# pblaze_ext.net
KiCad netlist of a schematic drawn in Altium Designer
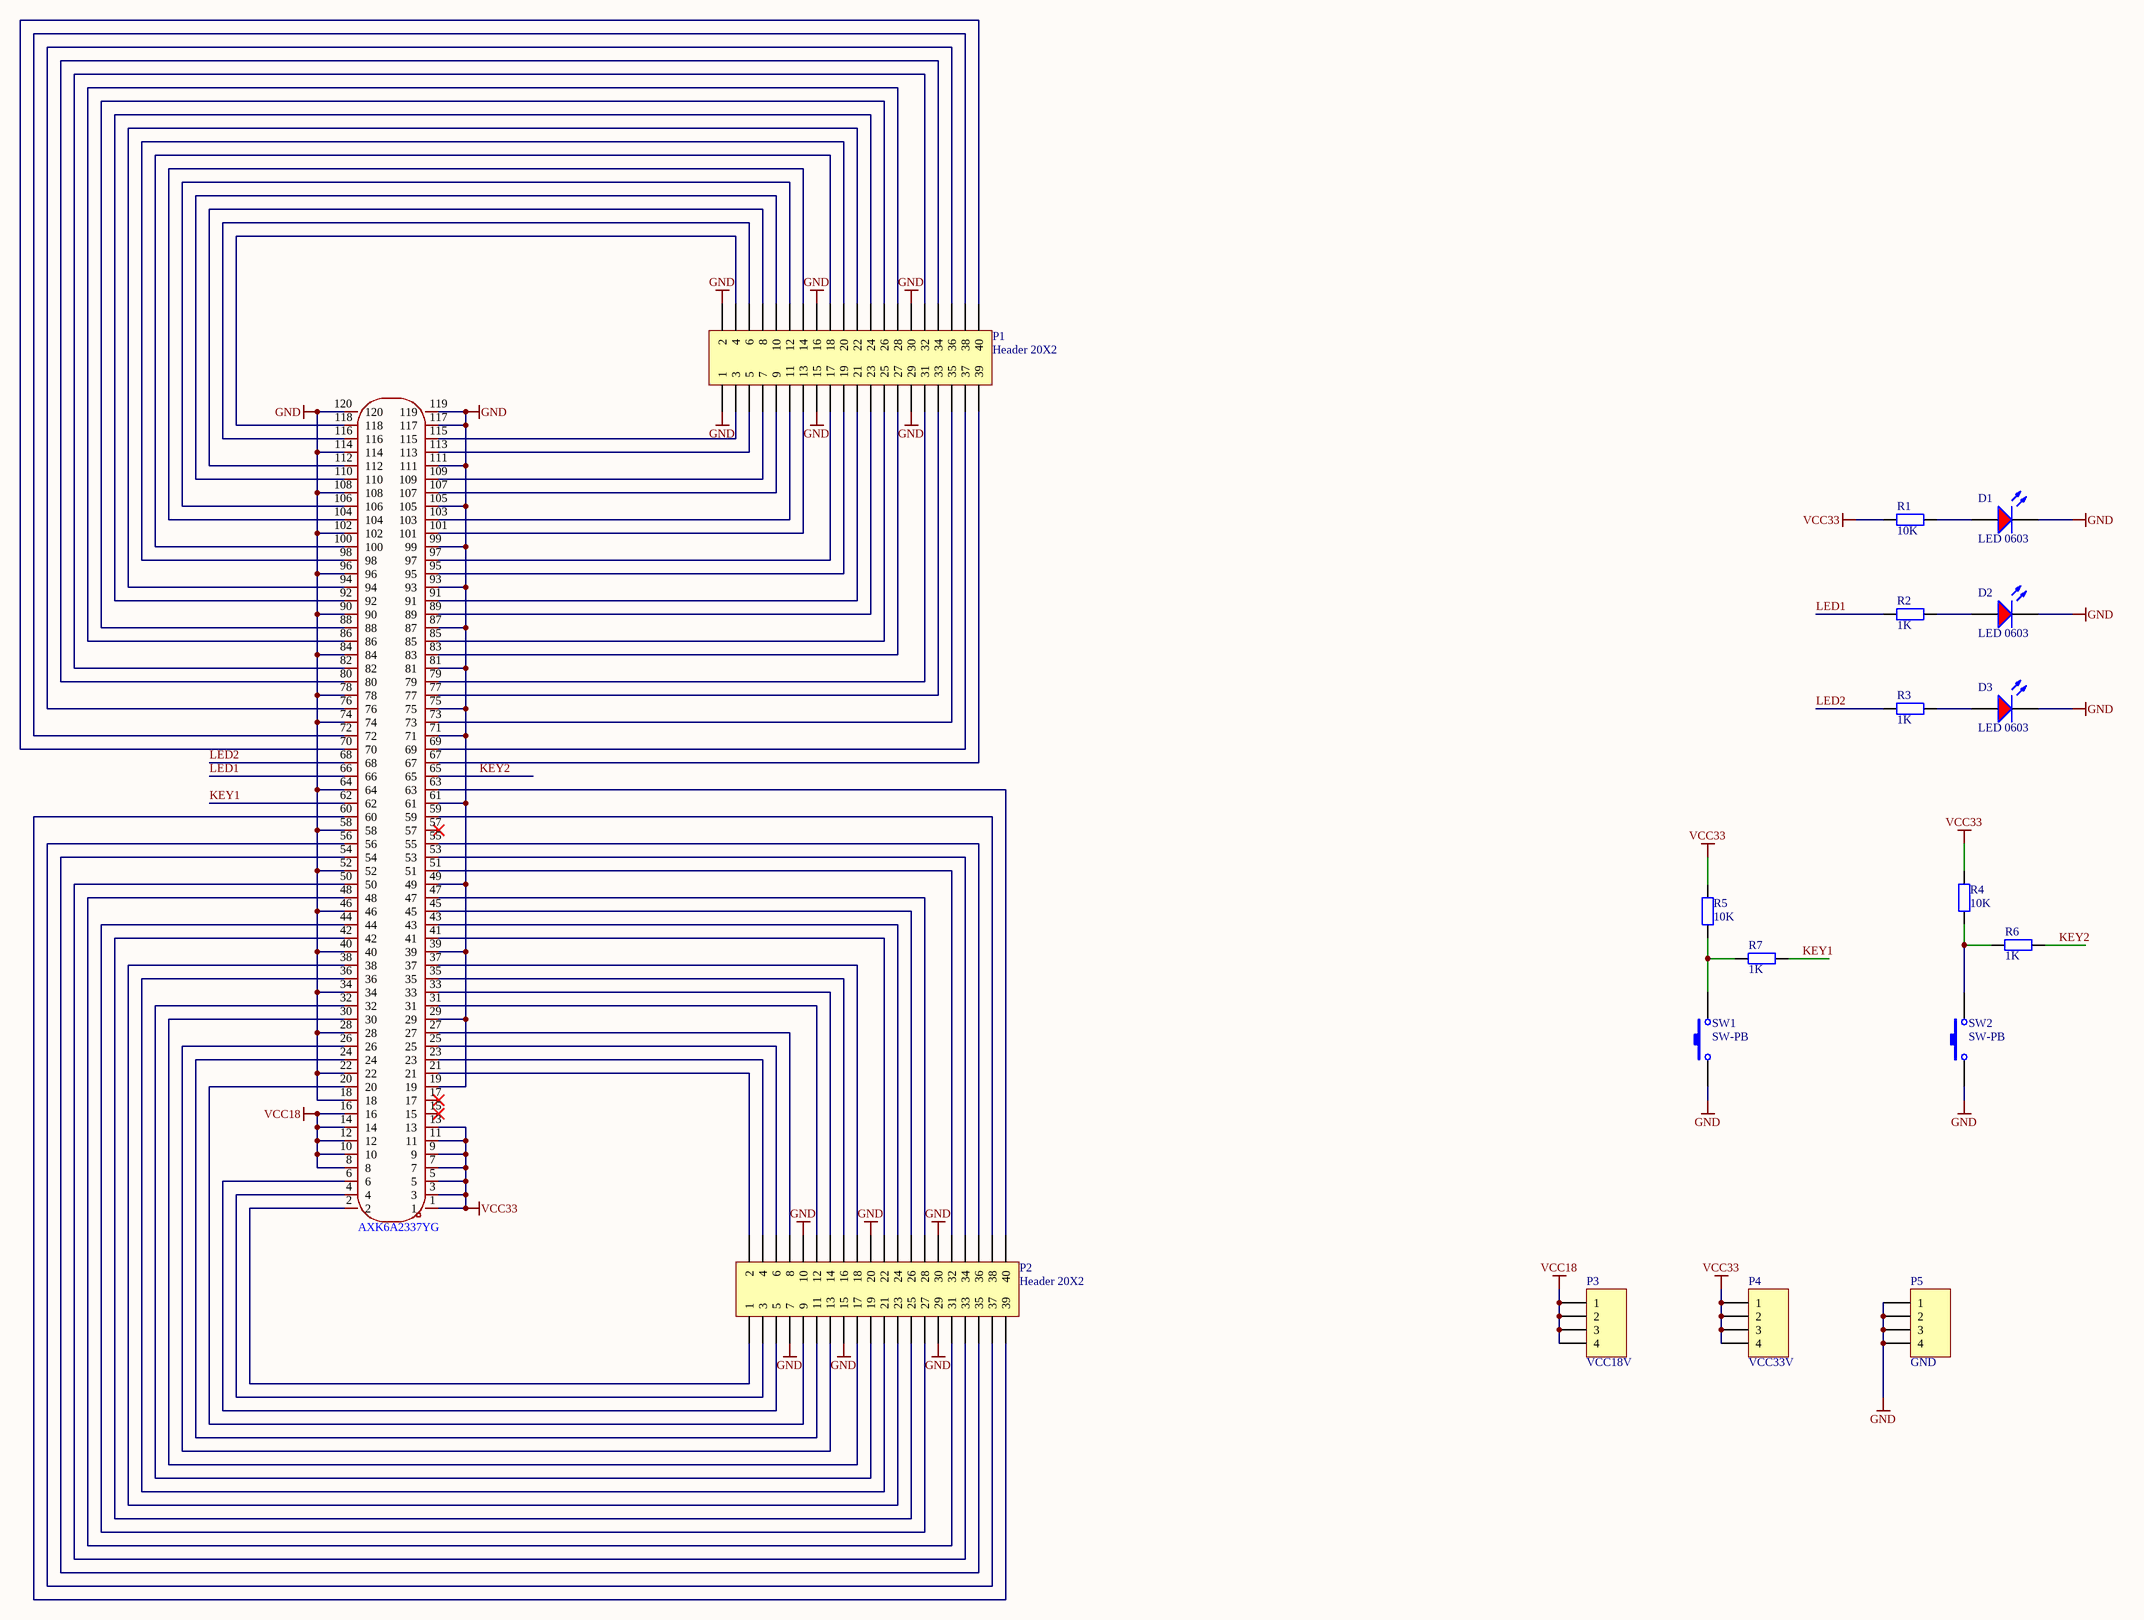
[diagram p0: pblaze_ext.schdoc]

(export (version "E")
  (design (tool "Eeschema 10.0.6"))
  (components
    (comp (ref "D1")
      (value "LED 0603")
      (footprint "0603_LED_S1")
      (description "发光二极管")
      (libsource (lib "Miscellaneous Devices LC") (part "0603 红灯"))
    )
    (comp (ref "D2")
      (value "LED 0603")
      (footprint "0603_LED_S1")
      (description "发光二极管")
      (libsource (lib "Miscellaneous Devices LC") (part "0603 红灯"))
    )
    (comp (ref "D3")
      (value "LED 0603")
      (footprint "0603_LED_S1")
      (description "发光二极管")
      (libsource (lib "Miscellaneous Devices LC") (part "0603 红灯"))
    )
    (comp (ref "P1")
      (value "Header 20X2")
      (footprint "HDR2X20")
      (description "Header, 20-Pin, Dual row")
      (fields (field (name "PUBLISHER") "Altium Limited"))
      (libsource (lib "Miscellaneous Connectors") (part "Header 20X2"))
    )
    (comp (ref "P2")
      (value "Header 20X2")
      (footprint "HDR2X20")
      (description "Header, 20-Pin, Dual row")
      (fields (field (name "PUBLISHER") "Altium Limited"))
      (libsource (lib "Miscellaneous Connectors") (part "Header 20X2"))
    )
    (comp (ref "P3")
      (value "VCC18V")
      (footprint "HDR1X4")
      (description "Header, 4-Pin")
      (fields (field (name "PUBLISHER") "Altium Limited"))
      (libsource (lib "Miscellaneous Connectors") (part "Header 4"))
    )
    (comp (ref "P4")
      (value "VCC33V")
      (footprint "HDR1X4")
      (description "Header, 4-Pin")
      (fields (field (name "PUBLISHER") "Altium Limited"))
      (libsource (lib "Miscellaneous Connectors") (part "Header 4"))
    )
    (comp (ref "P5")
      (value "GND")
      (footprint "HDR1X4")
      (description "Header, 4-Pin")
      (fields (field (name "PUBLISHER") "Altium Limited"))
      (libsource (lib "Miscellaneous Connectors") (part "Header 4"))
    )
    (comp (ref "R1")
      (value "10K")
      (footprint "0603_R")
      (description "贴片电阻")
      (libsource (lib "Miscellaneous Devices LC") (part "0603 1KΩ (1001) 1%"))
    )
    (comp (ref "R2")
      (value "1K")
      (footprint "0603_R")
      (description "贴片电阻")
      (libsource (lib "Miscellaneous Devices LC") (part "0603 1KΩ (1001) 1%"))
    )
    (comp (ref "R3")
      (value "1K")
      (footprint "0603_R")
      (description "贴片电阻")
      (libsource (lib "Miscellaneous Devices LC") (part "0603 1KΩ (1001) 1%"))
    )
    (comp (ref "R4")
      (value "10K")
      (footprint "0603_R")
      (description "贴片电阻")
      (libsource (lib "") (part "0603 1KΩ (1001) 1%_2"))
    )
    (comp (ref "R5")
      (value "10K")
      (footprint "0603_R")
      (description "贴片电阻")
      (libsource (lib "") (part "0603 1KΩ (1001) 1%_2"))
    )
    (comp (ref "R6")
      (value "1K")
      (footprint "0603_R")
      (description "贴片电阻")
      (libsource (lib "") (part "0603 1KΩ (1001) 1%_1"))
    )
    (comp (ref "R7")
      (value "1K")
      (footprint "0603_R")
      (description "贴片电阻")
      (libsource (lib "") (part "0603 1KΩ (1001) 1%_1"))
    )
    (comp (ref "SW1")
      (value "SW-PB")
      (footprint "SW-2- 3.8X7.6-S")
      (description "按钮开关")
      (fields (field (name "更新者") "安菲"))
      (libsource (lib "其他") (part "SW-PB"))
    )
    (comp (ref "SW2")
      (value "SW-PB")
      (footprint "SW-2- 3.8X7.6-S")
      (description "按钮开关")
      (fields (field (name "更新者") "安菲"))
      (libsource (lib "其他") (part "SW-PB"))
    )
    (comp (ref "U1")
      (value "AXK6A2337YG")
      (footprint "CONN-SMD_120P-P0.50_AXK6A2337YG")
      (fields (field (name "MANUFACTURER") "PANASONIC(松下)"))
      (libsource (lib "altium-import") (part "root_2_AXK6A2337YG_"))
    )
  )
  (nets
    (net (code "1") (name "/KEY1") (class "Default")
      (node (ref "R7") (pin "1") (pinfunction "1_1") (pintype "passive"))
      (node (ref "U1") (pin "62") (pinfunction "62_62") (pintype "passive"))
    )
    (net (code "2") (name "/KEY2") (class "Default")
      (node (ref "R6") (pin "1") (pinfunction "1_1") (pintype "passive"))
      (node (ref "U1") (pin "65") (pinfunction "65_65") (pintype "passive"))
    )
    (net (code "3") (name "/LED1") (class "Default")
      (node (ref "R2") (pin "1") (pinfunction "1_1") (pintype "passive"))
      (node (ref "U1") (pin "66") (pinfunction "66_66") (pintype "passive"))
    )
    (net (code "4") (name "/LED2") (class "Default")
      (node (ref "R3") (pin "1") (pinfunction "1_1") (pintype "passive"))
      (node (ref "U1") (pin "68") (pinfunction "68_68") (pintype "passive"))
    )
    (net (code "5") (name "GND") (class "Default")
      (node (ref "D1") (pin "K") (pinfunction "K_K") (pintype "passive"))
      (node (ref "D2") (pin "K") (pinfunction "K_K") (pintype "passive"))
      (node (ref "D3") (pin "K") (pinfunction "K_K") (pintype "passive"))
      (node (ref "P1") (pin "1") (pinfunction "1_1") (pintype "passive"))
      (node (ref "P1") (pin "15") (pinfunction "15_15") (pintype "passive"))
      (node (ref "P1") (pin "16") (pinfunction "16_16") (pintype "passive"))
      (node (ref "P1") (pin "2") (pinfunction "2_2") (pintype "passive"))
      (node (ref "P1") (pin "29") (pinfunction "29_29") (pintype "passive"))
      (node (ref "P1") (pin "30") (pinfunction "30_30") (pintype "passive"))
      (node (ref "P2") (pin "10") (pinfunction "10_10") (pintype "passive"))
      (node (ref "P2") (pin "15") (pinfunction "15_15") (pintype "passive"))
      (node (ref "P2") (pin "20") (pinfunction "20_20") (pintype "passive"))
      (node (ref "P2") (pin "29") (pinfunction "29_29") (pintype "passive"))
      (node (ref "P2") (pin "30") (pinfunction "30_30") (pintype "passive"))
      (node (ref "P2") (pin "7") (pinfunction "7_7") (pintype "passive"))
      (node (ref "P5") (pin "1") (pinfunction "1_1") (pintype "passive"))
      (node (ref "P5") (pin "2") (pinfunction "2_2") (pintype "passive"))
      (node (ref "P5") (pin "3") (pinfunction "3_3") (pintype "passive"))
      (node (ref "P5") (pin "4") (pinfunction "4_4") (pintype "passive"))
      (node (ref "SW1") (pin "1") (pinfunction "1_1") (pintype "passive"))
      (node (ref "SW2") (pin "1") (pinfunction "1_1") (pintype "passive"))
      (node (ref "U1") (pin "102") (pinfunction "102_102") (pintype "passive"))
      (node (ref "U1") (pin "105") (pinfunction "105_105") (pintype "passive"))
      (node (ref "U1") (pin "108") (pinfunction "108_108") (pintype "passive"))
      (node (ref "U1") (pin "111") (pinfunction "111_111") (pintype "passive"))
      (node (ref "U1") (pin "114") (pinfunction "114_114") (pintype "passive"))
      (node (ref "U1") (pin "117") (pinfunction "117_117") (pintype "passive"))
      (node (ref "U1") (pin "119") (pinfunction "119_119") (pintype "passive"))
      (node (ref "U1") (pin "120") (pinfunction "120_120") (pintype "passive"))
      (node (ref "U1") (pin "18") (pinfunction "18_18") (pintype "passive"))
      (node (ref "U1") (pin "19") (pinfunction "19_19") (pintype "passive"))
      (node (ref "U1") (pin "22") (pinfunction "22_22") (pintype "passive"))
      (node (ref "U1") (pin "28") (pinfunction "28_28") (pintype "passive"))
      (node (ref "U1") (pin "29") (pinfunction "29_29") (pintype "passive"))
      (node (ref "U1") (pin "34") (pinfunction "34_34") (pintype "passive"))
      (node (ref "U1") (pin "39") (pinfunction "39_39") (pintype "passive"))
      (node (ref "U1") (pin "40") (pinfunction "40_40") (pintype "passive"))
      (node (ref "U1") (pin "46") (pinfunction "46_46") (pintype "passive"))
      (node (ref "U1") (pin "49") (pinfunction "49_49") (pintype "passive"))
      (node (ref "U1") (pin "52") (pinfunction "52_52") (pintype "passive"))
      (node (ref "U1") (pin "58") (pinfunction "58_58") (pintype "passive"))
      (node (ref "U1") (pin "61") (pinfunction "61_61") (pintype "passive"))
      (node (ref "U1") (pin "64") (pinfunction "64_64") (pintype "passive"))
      (node (ref "U1") (pin "71") (pinfunction "71_71") (pintype "passive"))
      (node (ref "U1") (pin "74") (pinfunction "74_74") (pintype "passive"))
      (node (ref "U1") (pin "75") (pinfunction "75_75") (pintype "passive"))
      (node (ref "U1") (pin "78") (pinfunction "78_78") (pintype "passive"))
      (node (ref "U1") (pin "81") (pinfunction "81_81") (pintype "passive"))
      (node (ref "U1") (pin "84") (pinfunction "84_84") (pintype "passive"))
      (node (ref "U1") (pin "87") (pinfunction "87_87") (pintype "passive"))
      (node (ref "U1") (pin "90") (pinfunction "90_90") (pintype "passive"))
      (node (ref "U1") (pin "93") (pinfunction "93_93") (pintype "passive"))
      (node (ref "U1") (pin "96") (pinfunction "96_96") (pintype "passive"))
      (node (ref "U1") (pin "99") (pinfunction "99_99") (pintype "passive"))
    )
    (net (code "6") (name "Net-(D1-PadA)") (class "Default")
      (node (ref "D1") (pin "A") (pinfunction "A_A") (pintype "passive"))
      (node (ref "R1") (pin "2") (pinfunction "2_2") (pintype "passive"))
    )
    (net (code "7") (name "Net-(D2-PadA)") (class "Default")
      (node (ref "D2") (pin "A") (pinfunction "A_A") (pintype "passive"))
      (node (ref "R2") (pin "2") (pinfunction "2_2") (pintype "passive"))
    )
    (net (code "8") (name "Net-(D3-PadA)") (class "Default")
      (node (ref "D3") (pin "A") (pinfunction "A_A") (pintype "passive"))
      (node (ref "R3") (pin "2") (pinfunction "2_2") (pintype "passive"))
    )
    (net (code "9") (name "Net-(P1-Pad3)") (class "Default")
      (node (ref "P1") (pin "3") (pinfunction "3_3") (pintype "passive"))
      (node (ref "U1") (pin "115") (pinfunction "115_115") (pintype "passive"))
    )
    (net (code "10") (name "Net-(P1-Pad4)") (class "Default")
      (node (ref "P1") (pin "4") (pinfunction "4_4") (pintype "passive"))
      (node (ref "U1") (pin "118") (pinfunction "118_118") (pintype "passive"))
    )
    (net (code "11") (name "Net-(P1-Pad5)") (class "Default")
      (node (ref "P1") (pin "5") (pinfunction "5_5") (pintype "passive"))
      (node (ref "U1") (pin "113") (pinfunction "113_113") (pintype "passive"))
    )
    (net (code "12") (name "Net-(P1-Pad6)") (class "Default")
      (node (ref "P1") (pin "6") (pinfunction "6_6") (pintype "passive"))
      (node (ref "U1") (pin "116") (pinfunction "116_116") (pintype "passive"))
    )
    (net (code "13") (name "Net-(P1-Pad7)") (class "Default")
      (node (ref "P1") (pin "7") (pinfunction "7_7") (pintype "passive"))
      (node (ref "U1") (pin "109") (pinfunction "109_109") (pintype "passive"))
    )
    (net (code "14") (name "Net-(P1-Pad8)") (class "Default")
      (node (ref "P1") (pin "8") (pinfunction "8_8") (pintype "passive"))
      (node (ref "U1") (pin "112") (pinfunction "112_112") (pintype "passive"))
    )
    (net (code "15") (name "Net-(P1-Pad9)") (class "Default")
      (node (ref "P1") (pin "9") (pinfunction "9_9") (pintype "passive"))
      (node (ref "U1") (pin "107") (pinfunction "107_107") (pintype "passive"))
    )
    (net (code "16") (name "Net-(P1-Pad10)") (class "Default")
      (node (ref "P1") (pin "10") (pinfunction "10_10") (pintype "passive"))
      (node (ref "U1") (pin "110") (pinfunction "110_110") (pintype "passive"))
    )
    (net (code "17") (name "Net-(P1-Pad11)") (class "Default")
      (node (ref "P1") (pin "11") (pinfunction "11_11") (pintype "passive"))
      (node (ref "U1") (pin "103") (pinfunction "103_103") (pintype "passive"))
    )
    (net (code "18") (name "Net-(P1-Pad12)") (class "Default")
      (node (ref "P1") (pin "12") (pinfunction "12_12") (pintype "passive"))
      (node (ref "U1") (pin "106") (pinfunction "106_106") (pintype "passive"))
    )
    (net (code "19") (name "Net-(P1-Pad13)") (class "Default")
      (node (ref "P1") (pin "13") (pinfunction "13_13") (pintype "passive"))
      (node (ref "U1") (pin "101") (pinfunction "101_101") (pintype "passive"))
    )
    (net (code "20") (name "Net-(P1-Pad14)") (class "Default")
      (node (ref "P1") (pin "14") (pinfunction "14_14") (pintype "passive"))
      (node (ref "U1") (pin "104") (pinfunction "104_104") (pintype "passive"))
    )
    (net (code "21") (name "Net-(P1-Pad17)") (class "Default")
      (node (ref "P1") (pin "17") (pinfunction "17_17") (pintype "passive"))
      (node (ref "U1") (pin "97") (pinfunction "97_97") (pintype "passive"))
    )
    (net (code "22") (name "Net-(P1-Pad18)") (class "Default")
      (node (ref "P1") (pin "18") (pinfunction "18_18") (pintype "passive"))
      (node (ref "U1") (pin "100") (pinfunction "100_100") (pintype "passive"))
    )
    (net (code "23") (name "Net-(P1-Pad19)") (class "Default")
      (node (ref "P1") (pin "19") (pinfunction "19_19") (pintype "passive"))
      (node (ref "U1") (pin "95") (pinfunction "95_95") (pintype "passive"))
    )
    (net (code "24") (name "Net-(P1-Pad20)") (class "Default")
      (node (ref "P1") (pin "20") (pinfunction "20_20") (pintype "passive"))
      (node (ref "U1") (pin "98") (pinfunction "98_98") (pintype "passive"))
    )
    (net (code "25") (name "Net-(P1-Pad21)") (class "Default")
      (node (ref "P1") (pin "21") (pinfunction "21_21") (pintype "passive"))
      (node (ref "U1") (pin "91") (pinfunction "91_91") (pintype "passive"))
    )
    (net (code "26") (name "Net-(P1-Pad22)") (class "Default")
      (node (ref "P1") (pin "22") (pinfunction "22_22") (pintype "passive"))
      (node (ref "U1") (pin "94") (pinfunction "94_94") (pintype "passive"))
    )
    (net (code "27") (name "Net-(P1-Pad23)") (class "Default")
      (node (ref "P1") (pin "23") (pinfunction "23_23") (pintype "passive"))
      (node (ref "U1") (pin "89") (pinfunction "89_89") (pintype "passive"))
    )
    (net (code "28") (name "Net-(P1-Pad24)") (class "Default")
      (node (ref "P1") (pin "24") (pinfunction "24_24") (pintype "passive"))
      (node (ref "U1") (pin "92") (pinfunction "92_92") (pintype "passive"))
    )
    (net (code "29") (name "Net-(P1-Pad25)") (class "Default")
      (node (ref "P1") (pin "25") (pinfunction "25_25") (pintype "passive"))
      (node (ref "U1") (pin "85") (pinfunction "85_85") (pintype "passive"))
    )
    (net (code "30") (name "Net-(P1-Pad26)") (class "Default")
      (node (ref "P1") (pin "26") (pinfunction "26_26") (pintype "passive"))
      (node (ref "U1") (pin "88") (pinfunction "88_88") (pintype "passive"))
    )
    (net (code "31") (name "Net-(P1-Pad27)") (class "Default")
      (node (ref "P1") (pin "27") (pinfunction "27_27") (pintype "passive"))
      (node (ref "U1") (pin "83") (pinfunction "83_83") (pintype "passive"))
    )
    (net (code "32") (name "Net-(P1-Pad28)") (class "Default")
      (node (ref "P1") (pin "28") (pinfunction "28_28") (pintype "passive"))
      (node (ref "U1") (pin "86") (pinfunction "86_86") (pintype "passive"))
    )
    (net (code "33") (name "Net-(P1-Pad31)") (class "Default")
      (node (ref "P1") (pin "31") (pinfunction "31_31") (pintype "passive"))
      (node (ref "U1") (pin "79") (pinfunction "79_79") (pintype "passive"))
    )
    (net (code "34") (name "Net-(P1-Pad32)") (class "Default")
      (node (ref "P1") (pin "32") (pinfunction "32_32") (pintype "passive"))
      (node (ref "U1") (pin "82") (pinfunction "82_82") (pintype "passive"))
    )
    (net (code "35") (name "Net-(P1-Pad33)") (class "Default")
      (node (ref "P1") (pin "33") (pinfunction "33_33") (pintype "passive"))
      (node (ref "U1") (pin "77") (pinfunction "77_77") (pintype "passive"))
    )
    (net (code "36") (name "Net-(P1-Pad34)") (class "Default")
      (node (ref "P1") (pin "34") (pinfunction "34_34") (pintype "passive"))
      (node (ref "U1") (pin "80") (pinfunction "80_80") (pintype "passive"))
    )
    (net (code "37") (name "Net-(P1-Pad35)") (class "Default")
      (node (ref "P1") (pin "35") (pinfunction "35_35") (pintype "passive"))
      (node (ref "U1") (pin "73") (pinfunction "73_73") (pintype "passive"))
    )
    (net (code "38") (name "Net-(P1-Pad36)") (class "Default")
      (node (ref "P1") (pin "36") (pinfunction "36_36") (pintype "passive"))
      (node (ref "U1") (pin "76") (pinfunction "76_76") (pintype "passive"))
    )
    (net (code "39") (name "Net-(P1-Pad37)") (class "Default")
      (node (ref "P1") (pin "37") (pinfunction "37_37") (pintype "passive"))
      (node (ref "U1") (pin "69") (pinfunction "69_69") (pintype "passive"))
    )
    (net (code "40") (name "Net-(P1-Pad38)") (class "Default")
      (node (ref "P1") (pin "38") (pinfunction "38_38") (pintype "passive"))
      (node (ref "U1") (pin "72") (pinfunction "72_72") (pintype "passive"))
    )
    (net (code "41") (name "Net-(P1-Pad39)") (class "Default")
      (node (ref "P1") (pin "39") (pinfunction "39_39") (pintype "passive"))
      (node (ref "U1") (pin "67") (pinfunction "67_67") (pintype "passive"))
    )
    (net (code "42") (name "Net-(P1-Pad40)") (class "Default")
      (node (ref "P1") (pin "40") (pinfunction "40_40") (pintype "passive"))
      (node (ref "U1") (pin "70") (pinfunction "70_70") (pintype "passive"))
    )
    (net (code "43") (name "Net-(P2-Pad1)") (class "Default")
      (node (ref "P2") (pin "1") (pinfunction "1_1") (pintype "passive"))
      (node (ref "U1") (pin "2") (pinfunction "2_2") (pintype "passive"))
    )
    (net (code "44") (name "Net-(P2-Pad2)") (class "Default")
      (node (ref "P2") (pin "2") (pinfunction "2_2") (pintype "passive"))
      (node (ref "U1") (pin "21") (pinfunction "21_21") (pintype "passive"))
    )
    (net (code "45") (name "Net-(P2-Pad3)") (class "Default")
      (node (ref "P2") (pin "3") (pinfunction "3_3") (pintype "passive"))
      (node (ref "U1") (pin "4") (pinfunction "4_4") (pintype "passive"))
    )
    (net (code "46") (name "Net-(P2-Pad4)") (class "Default")
      (node (ref "P2") (pin "4") (pinfunction "4_4") (pintype "passive"))
      (node (ref "U1") (pin "23") (pinfunction "23_23") (pintype "passive"))
    )
    (net (code "47") (name "Net-(P2-Pad5)") (class "Default")
      (node (ref "P2") (pin "5") (pinfunction "5_5") (pintype "passive"))
      (node (ref "U1") (pin "6") (pinfunction "6_6") (pintype "passive"))
    )
    (net (code "48") (name "Net-(P2-Pad6)") (class "Default")
      (node (ref "P2") (pin "6") (pinfunction "6_6") (pintype "passive"))
      (node (ref "U1") (pin "25") (pinfunction "25_25") (pintype "passive"))
    )
    (net (code "49") (name "Net-(P2-Pad8)") (class "Default")
      (node (ref "P2") (pin "8") (pinfunction "8_8") (pintype "passive"))
      (node (ref "U1") (pin "27") (pinfunction "27_27") (pintype "passive"))
    )
    (net (code "50") (name "Net-(P2-Pad9)") (class "Default")
      (node (ref "P2") (pin "9") (pinfunction "9_9") (pintype "passive"))
      (node (ref "U1") (pin "20") (pinfunction "20_20") (pintype "passive"))
    )
    (net (code "51") (name "Net-(P2-Pad11)") (class "Default")
      (node (ref "P2") (pin "11") (pinfunction "11_11") (pintype "passive"))
      (node (ref "U1") (pin "24") (pinfunction "24_24") (pintype "passive"))
    )
    (net (code "52") (name "Net-(P2-Pad12)") (class "Default")
      (node (ref "P2") (pin "12") (pinfunction "12_12") (pintype "passive"))
      (node (ref "U1") (pin "31") (pinfunction "31_31") (pintype "passive"))
    )
    (net (code "53") (name "Net-(P2-Pad13)") (class "Default")
      (node (ref "P2") (pin "13") (pinfunction "13_13") (pintype "passive"))
      (node (ref "U1") (pin "26") (pinfunction "26_26") (pintype "passive"))
    )
    (net (code "54") (name "Net-(P2-Pad14)") (class "Default")
      (node (ref "P2") (pin "14") (pinfunction "14_14") (pintype "passive"))
      (node (ref "U1") (pin "33") (pinfunction "33_33") (pintype "passive"))
    )
    (net (code "55") (name "Net-(P2-Pad16)") (class "Default")
      (node (ref "P2") (pin "16") (pinfunction "16_16") (pintype "passive"))
      (node (ref "U1") (pin "35") (pinfunction "35_35") (pintype "passive"))
    )
    (net (code "56") (name "Net-(P2-Pad17)") (class "Default")
      (node (ref "P2") (pin "17") (pinfunction "17_17") (pintype "passive"))
      (node (ref "U1") (pin "30") (pinfunction "30_30") (pintype "passive"))
    )
    (net (code "57") (name "Net-(P2-Pad18)") (class "Default")
      (node (ref "P2") (pin "18") (pinfunction "18_18") (pintype "passive"))
      (node (ref "U1") (pin "37") (pinfunction "37_37") (pintype "passive"))
    )
    (net (code "58") (name "Net-(P2-Pad19)") (class "Default")
      (node (ref "P2") (pin "19") (pinfunction "19_19") (pintype "passive"))
      (node (ref "U1") (pin "32") (pinfunction "32_32") (pintype "passive"))
    )
    (net (code "59") (name "Net-(P2-Pad21)") (class "Default")
      (node (ref "P2") (pin "21") (pinfunction "21_21") (pintype "passive"))
      (node (ref "U1") (pin "36") (pinfunction "36_36") (pintype "passive"))
    )
    (net (code "60") (name "Net-(P2-Pad22)") (class "Default")
      (node (ref "P2") (pin "22") (pinfunction "22_22") (pintype "passive"))
      (node (ref "U1") (pin "41") (pinfunction "41_41") (pintype "passive"))
    )
    (net (code "61") (name "Net-(P2-Pad23)") (class "Default")
      (node (ref "P2") (pin "23") (pinfunction "23_23") (pintype "passive"))
      (node (ref "U1") (pin "38") (pinfunction "38_38") (pintype "passive"))
    )
    (net (code "62") (name "Net-(P2-Pad24)") (class "Default")
      (node (ref "P2") (pin "24") (pinfunction "24_24") (pintype "passive"))
      (node (ref "U1") (pin "43") (pinfunction "43_43") (pintype "passive"))
    )
    (net (code "63") (name "Net-(P2-Pad25)") (class "Default")
      (node (ref "P2") (pin "25") (pinfunction "25_25") (pintype "passive"))
      (node (ref "U1") (pin "42") (pinfunction "42_42") (pintype "passive"))
    )
    (net (code "64") (name "Net-(P2-Pad26)") (class "Default")
      (node (ref "P2") (pin "26") (pinfunction "26_26") (pintype "passive"))
      (node (ref "U1") (pin "45") (pinfunction "45_45") (pintype "passive"))
    )
    (net (code "65") (name "Net-(P2-Pad27)") (class "Default")
      (node (ref "P2") (pin "27") (pinfunction "27_27") (pintype "passive"))
      (node (ref "U1") (pin "44") (pinfunction "44_44") (pintype "passive"))
    )
    (net (code "66") (name "Net-(P2-Pad28)") (class "Default")
      (node (ref "P2") (pin "28") (pinfunction "28_28") (pintype "passive"))
      (node (ref "U1") (pin "47") (pinfunction "47_47") (pintype "passive"))
    )
    (net (code "67") (name "Net-(P2-Pad31)") (class "Default")
      (node (ref "P2") (pin "31") (pinfunction "31_31") (pintype "passive"))
      (node (ref "U1") (pin "48") (pinfunction "48_48") (pintype "passive"))
    )
    (net (code "68") (name "Net-(P2-Pad32)") (class "Default")
      (node (ref "P2") (pin "32") (pinfunction "32_32") (pintype "passive"))
      (node (ref "U1") (pin "51") (pinfunction "51_51") (pintype "passive"))
    )
    (net (code "69") (name "Net-(P2-Pad33)") (class "Default")
      (node (ref "P2") (pin "33") (pinfunction "33_33") (pintype "passive"))
      (node (ref "U1") (pin "50") (pinfunction "50_50") (pintype "passive"))
    )
    (net (code "70") (name "Net-(P2-Pad34)") (class "Default")
      (node (ref "P2") (pin "34") (pinfunction "34_34") (pintype "passive"))
      (node (ref "U1") (pin "53") (pinfunction "53_53") (pintype "passive"))
    )
    (net (code "71") (name "Net-(P2-Pad35)") (class "Default")
      (node (ref "P2") (pin "35") (pinfunction "35_35") (pintype "passive"))
      (node (ref "U1") (pin "54") (pinfunction "54_54") (pintype "passive"))
    )
    (net (code "72") (name "Net-(P2-Pad36)") (class "Default")
      (node (ref "P2") (pin "36") (pinfunction "36_36") (pintype "passive"))
      (node (ref "U1") (pin "55") (pinfunction "55_55") (pintype "passive"))
    )
    (net (code "73") (name "Net-(P2-Pad37)") (class "Default")
      (node (ref "P2") (pin "37") (pinfunction "37_37") (pintype "passive"))
      (node (ref "U1") (pin "56") (pinfunction "56_56") (pintype "passive"))
    )
    (net (code "74") (name "Net-(P2-Pad38)") (class "Default")
      (node (ref "P2") (pin "38") (pinfunction "38_38") (pintype "passive"))
      (node (ref "U1") (pin "59") (pinfunction "59_59") (pintype "passive"))
    )
    (net (code "75") (name "Net-(P2-Pad39)") (class "Default")
      (node (ref "P2") (pin "39") (pinfunction "39_39") (pintype "passive"))
      (node (ref "U1") (pin "60") (pinfunction "60_60") (pintype "passive"))
    )
    (net (code "76") (name "Net-(P2-Pad40)") (class "Default")
      (node (ref "P2") (pin "40") (pinfunction "40_40") (pintype "passive"))
      (node (ref "U1") (pin "63") (pinfunction "63_63") (pintype "passive"))
    )
    (net (code "77") (name "Net-(R4-Pad1)") (class "Default")
      (node (ref "R4") (pin "1") (pinfunction "1_1") (pintype "passive"))
      (node (ref "R6") (pin "2") (pinfunction "2_2") (pintype "passive"))
      (node (ref "SW2") (pin "2") (pinfunction "2_2") (pintype "passive"))
    )
    (net (code "78") (name "Net-(R5-Pad1)") (class "Default")
      (node (ref "R5") (pin "1") (pinfunction "1_1") (pintype "passive"))
      (node (ref "R7") (pin "2") (pinfunction "2_2") (pintype "passive"))
      (node (ref "SW1") (pin "2") (pinfunction "2_2") (pintype "passive"))
    )
    (net (code "79") (name "VCC18") (class "Default")
      (node (ref "P3") (pin "1") (pinfunction "1_1") (pintype "passive"))
      (node (ref "P3") (pin "2") (pinfunction "2_2") (pintype "passive"))
      (node (ref "P3") (pin "3") (pinfunction "3_3") (pintype "passive"))
      (node (ref "P3") (pin "4") (pinfunction "4_4") (pintype "passive"))
      (node (ref "U1") (pin "10") (pinfunction "10_10") (pintype "passive"))
      (node (ref "U1") (pin "12") (pinfunction "12_12") (pintype "passive"))
      (node (ref "U1") (pin "14") (pinfunction "14_14") (pintype "passive"))
      (node (ref "U1") (pin "16") (pinfunction "16_16") (pintype "passive"))
      (node (ref "U1") (pin "8") (pinfunction "8_8") (pintype "passive"))
    )
    (net (code "80") (name "VCC33") (class "Default")
      (node (ref "P4") (pin "1") (pinfunction "1_1") (pintype "passive"))
      (node (ref "P4") (pin "2") (pinfunction "2_2") (pintype "passive"))
      (node (ref "P4") (pin "3") (pinfunction "3_3") (pintype "passive"))
      (node (ref "P4") (pin "4") (pinfunction "4_4") (pintype "passive"))
      (node (ref "R1") (pin "1") (pinfunction "1_1") (pintype "passive"))
      (node (ref "R4") (pin "2") (pinfunction "2_2") (pintype "passive"))
      (node (ref "R5") (pin "2") (pinfunction "2_2") (pintype "passive"))
      (node (ref "U1") (pin "1") (pinfunction "1_1") (pintype "passive"))
      (node (ref "U1") (pin "11") (pinfunction "11_11") (pintype "passive"))
      (node (ref "U1") (pin "13") (pinfunction "13_13") (pintype "passive"))
      (node (ref "U1") (pin "3") (pinfunction "3_3") (pintype "passive"))
      (node (ref "U1") (pin "5") (pinfunction "5_5") (pintype "passive"))
      (node (ref "U1") (pin "7") (pinfunction "7_7") (pintype "passive"))
      (node (ref "U1") (pin "9") (pinfunction "9_9") (pintype "passive"))
    )
    (net (code "81") (name "unconnected-(U1-Pad15)") (class "Default")
      (node (ref "U1") (pin "15") (pinfunction "15_15") (pintype "passive+no_connect"))
    )
    (net (code "82") (name "unconnected-(U1-Pad17)") (class "Default")
      (node (ref "U1") (pin "17") (pinfunction "17_17") (pintype "passive+no_connect"))
    )
    (net (code "83") (name "unconnected-(U1-Pad57)") (class "Default")
      (node (ref "U1") (pin "57") (pinfunction "57_57") (pintype "passive+no_connect"))
    )
  )
)
